# 05_MICROSD.net
KiCad netlist of a schematic drawn in Altium Designer
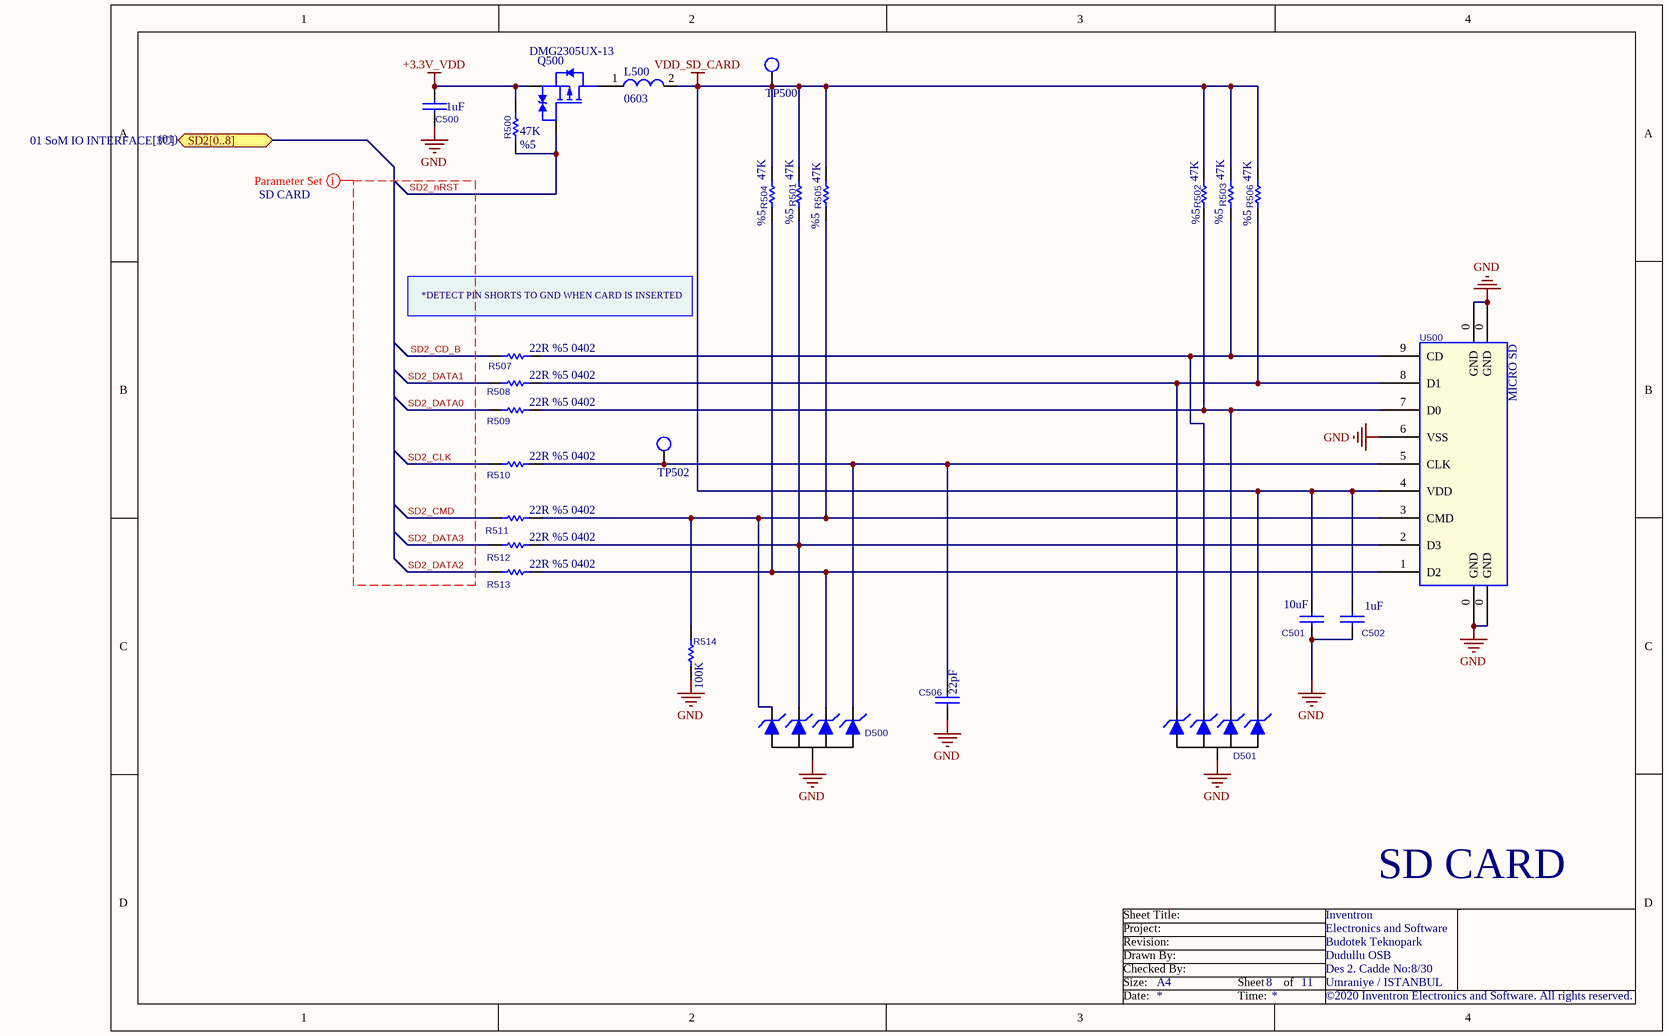
[diagram p0: 05 MICROSD.SchDoc]

(export (version "E")
  (design (tool "Eeschema 10.0.6"))
  (components
    (comp (ref "C500")
      (value "1uF")
      (footprint "0603_CC")
      (description "CAP CER 1UF 25V X7R 0603")
      (fields (field (name "CREATED BY") "LA") (field (name "CHECKED BY") "*"))
      (libsource (lib "ARETE_SCH") (part "CAP-CL10B105KA8NNNC"))
    )
    (comp (ref "C501")
      (value "10uF")
      (footprint "0603_CC")
      (description "CAP CER 10UF 6.3V X6S 0603")
      (fields (field (name "CREATED BY") "LA") (field (name "CHECKED BY") "*"))
      (libsource (lib "ARETE_SCH") (part "CAP-JMK107BC6106MA-T"))
    )
    (comp (ref "C502")
      (value "1uF")
      (footprint "0603_CC")
      (description "CAP CER 1UF 25V X7R 0603")
      (fields (field (name "CREATED BY") "LA") (field (name "CHECKED BY") "*"))
      (libsource (lib "ARETE_SCH") (part "CAP-CL10B105KA8NNNC"))
    )
    (comp (ref "C506")
      (value "22pF")
      (footprint "0402_CC")
      (description "CAP CER 22PF 50V C0G/NPO 0402")
      (fields (field (name "CREATED BY") "LA") (field (name "CHECKED BY") "*"))
      (libsource (lib "ARETE_SCH") (part "CAP-C0402C220K5GACTU"))
    )
    (comp (ref "D500")
      (value "DIODE-DF5A6.2LJE,LM")
      (footprint "DF5A6.2LJE,LM")
      (description "TVS DIODE 5V 4CH SOT-553")
      (fields (field (name "CREATED BY") "OKS") (field (name "CHECKED BY") "*"))
      (libsource (lib "ARETE_SCH") (part "DIODE-DF5A6.2LJE,LM"))
    )
    (comp (ref "D501")
      (value "DIODE-DF5A6.2LJE,LM")
      (footprint "DF5A6.2LJE,LM")
      (description "TVS DIODE 5V 4CH SOT-553")
      (fields (field (name "CREATED BY") "OKS") (field (name "CHECKED BY") "*"))
      (libsource (lib "ARETE_SCH") (part "DIODE-DF5A6.2LJE,LM"))
    )
    (comp (ref "L500")
      (value "0603")
      (footprint "0603_RES")
      (description "0OHM 0603")
      (fields (field (name "CREATED BY") "EE") (field (name "CHECKED BY") "*"))
      (libsource (lib "ARETE_SCH") (part "IND-FERRITE (RES 0 OHM) 0603"))
    )
    (comp (ref "Q500")
      (value "DMG2305UX-13")
      (footprint "SOT23")
      (description "MOSFET P-CH 20V 4.2A SOT23")
      (fields (field (name "CREATED BY") "EE") (field (name "CHECKED BY") "*"))
      (libsource (lib "ARETE_SCH") (part "MOS-DMG2305UX-13"))
    )
    (comp (ref "R500")
      (value "47K")
      (footprint "0402_RES")
      (description "RES 47K OHM 5% 1/16W 0402")
      (fields
        (field (name "TOLERANCE") "%5")
        (field (name "CREATED BY") "LA")
        (field (name "CHECKED BY") "*")
      )
      (libsource (lib "ARETE_SCH") (part "RES-47K"))
    )
    (comp (ref "R501")
      (value "47K")
      (footprint "0402_RES")
      (description "RES 47K OHM 5% 1/16W 0402")
      (fields
        (field (name "TOLERANCE") "%5")
        (field (name "CREATED BY") "LA")
        (field (name "CHECKED BY") "*")
      )
      (libsource (lib "ARETE_SCH") (part "RES-47K"))
    )
    (comp (ref "R502")
      (value "47K")
      (footprint "0402_RES")
      (description "RES 47K OHM 5% 1/16W 0402")
      (fields
        (field (name "TOLERANCE") "%5")
        (field (name "CREATED BY") "LA")
        (field (name "CHECKED BY") "*")
      )
      (libsource (lib "ARETE_SCH") (part "RES-47K"))
    )
    (comp (ref "R503")
      (value "47K")
      (footprint "0402_RES")
      (description "RES 47K OHM 5% 1/16W 0402")
      (fields
        (field (name "TOLERANCE") "%5")
        (field (name "CREATED BY") "LA")
        (field (name "CHECKED BY") "*")
      )
      (libsource (lib "ARETE_SCH") (part "RES-47K"))
    )
    (comp (ref "R504")
      (value "47K")
      (footprint "0402_RES")
      (description "RES 47K OHM 5% 1/16W 0402")
      (fields
        (field (name "TOLERANCE") "%5")
        (field (name "CREATED BY") "LA")
        (field (name "CHECKED BY") "*")
      )
      (libsource (lib "ARETE_SCH") (part "RES-47K"))
    )
    (comp (ref "R505")
      (value "47K")
      (footprint "0402_RES")
      (description "RES 47K OHM 5% 1/16W 0402")
      (fields
        (field (name "TOLERANCE") "%5")
        (field (name "CREATED BY") "LA")
        (field (name "CHECKED BY") "*")
      )
      (libsource (lib "ARETE_SCH") (part "RES-47K"))
    )
    (comp (ref "R506")
      (value "47K")
      (footprint "0402_RES")
      (description "RES 47K OHM 5% 1/16W 0402")
      (fields
        (field (name "TOLERANCE") "%5")
        (field (name "CREATED BY") "LA")
        (field (name "CHECKED BY") "*")
      )
      (libsource (lib "ARETE_SCH") (part "RES-47K"))
    )
    (comp (ref "R507")
      (value "22R %5 0402")
      (footprint "0402_RES")
      (description "RES, THICK FILM, 22R, 5%, 0.0625W, 0402, REEL")
      (fields (field (name "CREATED BY") "E.E") (field (name "CHECKED BY") "*"))
      (libsource (lib "ARETE_SCH") (part "RES- RC0402JR-0722RL."))
    )
    (comp (ref "R508")
      (value "22R %5 0402")
      (footprint "0402_RES")
      (description "RES, THICK FILM, 22R, 5%, 0.0625W, 0402, REEL")
      (fields (field (name "CREATED BY") "E.E") (field (name "CHECKED BY") "*"))
      (libsource (lib "ARETE_SCH") (part "RES- RC0402JR-0722RL."))
    )
    (comp (ref "R509")
      (value "22R %5 0402")
      (footprint "0402_RES")
      (description "RES, THICK FILM, 22R, 5%, 0.0625W, 0402, REEL")
      (fields (field (name "CREATED BY") "E.E") (field (name "CHECKED BY") "*"))
      (libsource (lib "ARETE_SCH") (part "RES- RC0402JR-0722RL."))
    )
    (comp (ref "R510")
      (value "22R %5 0402")
      (footprint "0402_RES")
      (description "RES, THICK FILM, 22R, 5%, 0.0625W, 0402, REEL")
      (fields (field (name "CREATED BY") "E.E") (field (name "CHECKED BY") "*"))
      (libsource (lib "ARETE_SCH") (part "RES- RC0402JR-0722RL."))
    )
    (comp (ref "R511")
      (value "22R %5 0402")
      (footprint "0402_RES")
      (description "RES, THICK FILM, 22R, 5%, 0.0625W, 0402, REEL")
      (fields (field (name "CREATED BY") "E.E") (field (name "CHECKED BY") "*"))
      (libsource (lib "ARETE_SCH") (part "RES- RC0402JR-0722RL."))
    )
    (comp (ref "R512")
      (value "22R %5 0402")
      (footprint "0402_RES")
      (description "RES, THICK FILM, 22R, 5%, 0.0625W, 0402, REEL")
      (fields (field (name "CREATED BY") "E.E") (field (name "CHECKED BY") "*"))
      (libsource (lib "ARETE_SCH") (part "RES- RC0402JR-0722RL."))
    )
    (comp (ref "R513")
      (value "22R %5 0402")
      (footprint "0402_RES")
      (description "RES, THICK FILM, 22R, 5%, 0.0625W, 0402, REEL")
      (fields (field (name "CREATED BY") "E.E") (field (name "CHECKED BY") "*"))
      (libsource (lib "ARETE_SCH") (part "RES- RC0402JR-0722RL."))
    )
    (comp (ref "R514")
      (value "100K")
      (footprint "0402_RES")
      (description "RES 100K OHM 5% 1/16W 0402")
      (fields
        (field (name "TOLERANCE") "%5")
        (field (name "CREATED BY") "LA")
        (field (name "CHECKED BY") "*")
      )
      (libsource (lib "ARETE_SCH") (part "RES-RMCF0402JT100K"))
    )
    (comp (ref "TP500")
      (value "TEST POINT 15")
      (footprint "testpoint_15")
      (libsource (lib "X98_CARRIER_V1R2") (part "TEST POINT 15"))
    )
    (comp (ref "TP502")
      (value "TEST POINT 15")
      (footprint "testpoint_15")
      (libsource (lib "X98_CARRIER_V1R2") (part "TEST POINT 15"))
    )
    (comp (ref "U500")
      (value "MICRO SD")
      (footprint "L-KLS1-TF-003-H1.85-R")
      (description "CONECTOR MICRO SD CARD SMD KLS")
      (fields (field (name "CREATED BY") "LA") (field (name "CHECKED BY") "*"))
      (libsource (lib "ARETE_SCH") (part "CON-L-KLS1-TF-003-H1.85-R"))
    )
  )
  (nets
    (net (code "10") (name "+3.3V_VDD") (class "Default")
      (node (ref "C500") (pin "1") (pinfunction "1_1") (pintype "passive"))
      (node (ref "Q500") (pin "2") (pinfunction "S_2") (pintype "passive"))
      (node (ref "R500") (pin "2") (pinfunction "2_2") (pintype "passive"))
    )
    (net (code "12") (name "/SD2_CD_B") (class "Default")
      (node (ref "R507") (pin "1") (pinfunction "1_1") (pintype "passive"))
    )
    (net (code "13") (name "/SD2_CLK") (class "Default")
      (node (ref "R510") (pin "1") (pinfunction "1_1") (pintype "passive"))
    )
    (net (code "14") (name "/SD2_CMD") (class "Default")
      (node (ref "R511") (pin "1") (pinfunction "1_1") (pintype "passive"))
    )
    (net (code "15") (name "/SD2_DATA0") (class "Default")
      (node (ref "R509") (pin "1") (pinfunction "1_1") (pintype "passive"))
    )
    (net (code "16") (name "/SD2_DATA1") (class "Default")
      (node (ref "R508") (pin "1") (pinfunction "1_1") (pintype "passive"))
    )
    (net (code "17") (name "/SD2_DATA2") (class "Default")
      (node (ref "R513") (pin "1") (pinfunction "1_1") (pintype "passive"))
    )
    (net (code "18") (name "/SD2_DATA3") (class "Default")
      (node (ref "R512") (pin "1") (pinfunction "1_1") (pintype "passive"))
    )
    (net (code "19") (name "/SD2_nRST") (class "Default")
      (node (ref "Q500") (pin "1") (pinfunction "G_1") (pintype "passive"))
      (node (ref "R500") (pin "1") (pinfunction "1_1") (pintype "passive"))
    )
    (net (code "20") (name "GND") (class "Default")
      (node (ref "C500") (pin "2") (pinfunction "2_2") (pintype "passive"))
      (node (ref "C501") (pin "2") (pinfunction "2_2") (pintype "passive"))
      (node (ref "C502") (pin "2") (pinfunction "2_2") (pintype "passive"))
      (node (ref "C506") (pin "2") (pinfunction "2_2") (pintype "passive"))
      (node (ref "D500") (pin "2") (pinfunction "2_2") (pintype "passive"))
      (node (ref "D501") (pin "2") (pinfunction "2_2") (pintype "passive"))
      (node (ref "R514") (pin "1") (pinfunction "1_1") (pintype "passive"))
      (node (ref "U500") (pin "0") (pinfunction "GND_0") (pintype "passive"))
      (node (ref "U500") (pin "6") (pinfunction "VSS_6") (pintype "passive"))
    )
    (net (code "21") (name "Net-(Q500-D)") (class "Default")
      (node (ref "L500") (pin "1") (pinfunction "1_1") (pintype "passive"))
      (node (ref "Q500") (pin "3") (pinfunction "D_3") (pintype "passive"))
    )
    (net (code "22") (name "Net-(U500-CD)") (class "Default")
      (node (ref "D501") (pin "3") (pinfunction "3_3") (pintype "passive"))
      (node (ref "R503") (pin "1") (pinfunction "1_1") (pintype "passive"))
      (node (ref "R507") (pin "2") (pinfunction "2_2") (pintype "passive"))
      (node (ref "U500") (pin "9") (pinfunction "CD_9") (pintype "passive"))
    )
    (net (code "23") (name "Net-(U500-CLK)") (class "Default")
      (node (ref "C506") (pin "1") (pinfunction "1_1") (pintype "passive"))
      (node (ref "D500") (pin "5") (pinfunction "5_5") (pintype "passive"))
      (node (ref "R510") (pin "2") (pinfunction "2_2") (pintype "passive"))
      (node (ref "TP502") (pin "1") (pinfunction "1_1") (pintype "passive"))
      (node (ref "U500") (pin "5") (pinfunction "CLK_5") (pintype "passive"))
    )
    (net (code "24") (name "Net-(U500-CMD)") (class "Default")
      (node (ref "D500") (pin "1") (pinfunction "1_1") (pintype "passive"))
      (node (ref "R505") (pin "1") (pinfunction "1_1") (pintype "passive"))
      (node (ref "R511") (pin "2") (pinfunction "2_2") (pintype "passive"))
      (node (ref "R514") (pin "2") (pinfunction "2_2") (pintype "passive"))
      (node (ref "U500") (pin "3") (pinfunction "CMD_3") (pintype "passive"))
    )
    (net (code "25") (name "Net-(U500-D0)") (class "Default")
      (node (ref "D501") (pin "4") (pinfunction "4_4") (pintype "passive"))
      (node (ref "R502") (pin "1") (pinfunction "1_1") (pintype "passive"))
      (node (ref "R509") (pin "2") (pinfunction "2_2") (pintype "passive"))
      (node (ref "U500") (pin "7") (pinfunction "D0_7") (pintype "passive"))
    )
    (net (code "26") (name "Net-(U500-D1)") (class "Default")
      (node (ref "D501") (pin "1") (pinfunction "1_1") (pintype "passive"))
      (node (ref "R506") (pin "1") (pinfunction "1_1") (pintype "passive"))
      (node (ref "R508") (pin "2") (pinfunction "2_2") (pintype "passive"))
      (node (ref "U500") (pin "8") (pinfunction "D1_8") (pintype "passive"))
    )
    (net (code "27") (name "Net-(U500-D2)") (class "Default")
      (node (ref "D500") (pin "4") (pinfunction "4_4") (pintype "passive"))
      (node (ref "R504") (pin "1") (pinfunction "1_1") (pintype "passive"))
      (node (ref "R513") (pin "2") (pinfunction "2_2") (pintype "passive"))
      (node (ref "U500") (pin "1") (pinfunction "D2_1") (pintype "passive"))
    )
    (net (code "28") (name "Net-(U500-D3)") (class "Default")
      (node (ref "D500") (pin "3") (pinfunction "3_3") (pintype "passive"))
      (node (ref "R501") (pin "1") (pinfunction "1_1") (pintype "passive"))
      (node (ref "R512") (pin "2") (pinfunction "2_2") (pintype "passive"))
      (node (ref "U500") (pin "2") (pinfunction "D3_2") (pintype "passive"))
    )
    (net (code "29") (name "VDD_SD_CARD") (class "Default")
      (node (ref "C501") (pin "1") (pinfunction "1_1") (pintype "passive"))
      (node (ref "C502") (pin "1") (pinfunction "1_1") (pintype "passive"))
      (node (ref "D501") (pin "5") (pinfunction "5_5") (pintype "passive"))
      (node (ref "L500") (pin "2") (pinfunction "2_2") (pintype "passive"))
      (node (ref "R501") (pin "2") (pinfunction "2_2") (pintype "passive"))
      (node (ref "R502") (pin "2") (pinfunction "2_2") (pintype "passive"))
      (node (ref "R503") (pin "2") (pinfunction "2_2") (pintype "passive"))
      (node (ref "R504") (pin "2") (pinfunction "2_2") (pintype "passive"))
      (node (ref "R505") (pin "2") (pinfunction "2_2") (pintype "passive"))
      (node (ref "R506") (pin "2") (pinfunction "2_2") (pintype "passive"))
      (node (ref "TP500") (pin "1") (pinfunction "1_1") (pintype "passive"))
      (node (ref "U500") (pin "4") (pinfunction "VDD_4") (pintype "passive"))
    )
  )
)
